# MSP430Geiger.net
KiCad netlist of a schematic drawn in EAGLE
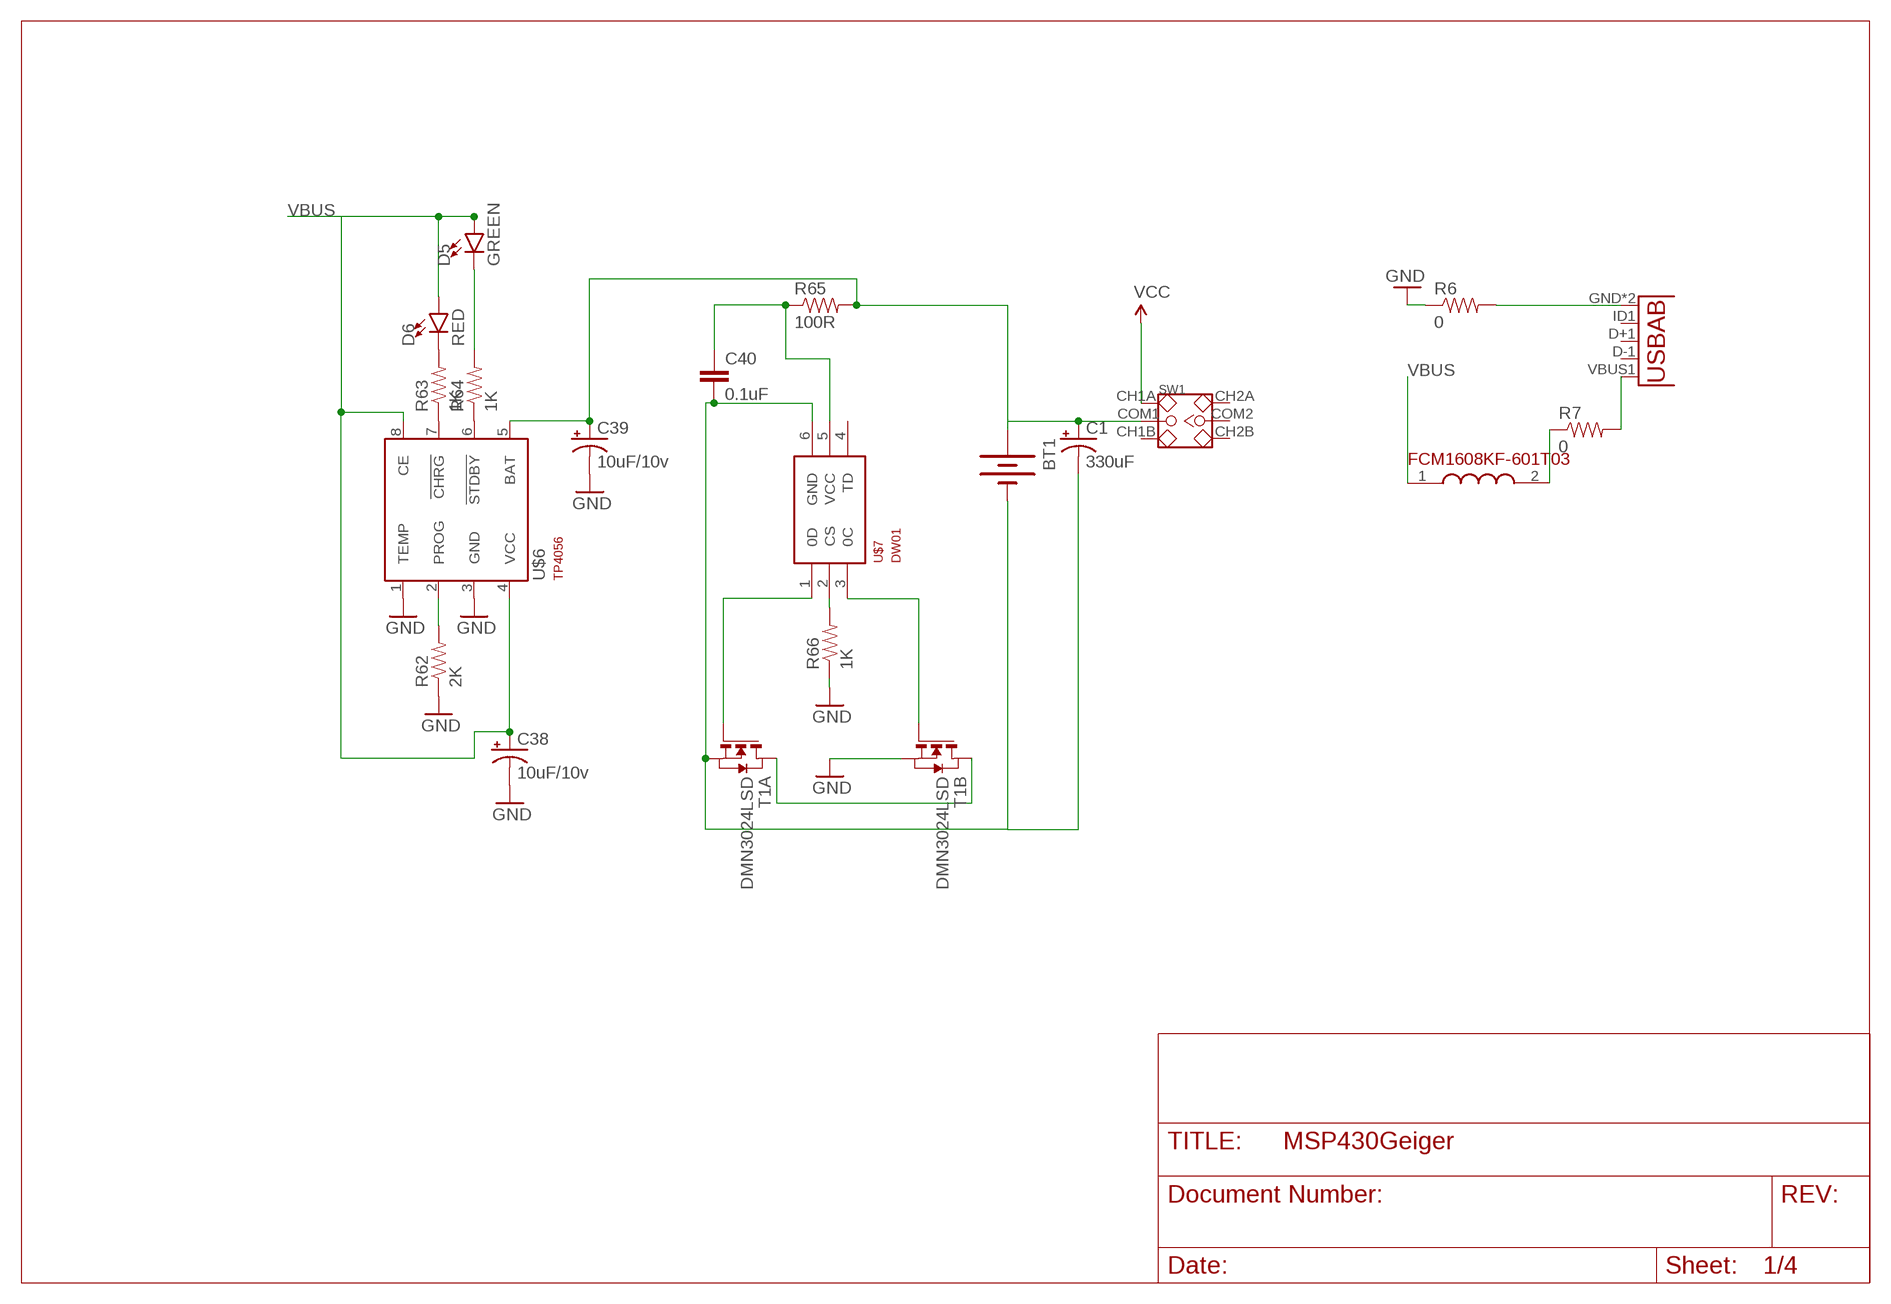
[diagram p0: schematic, sheet 1]
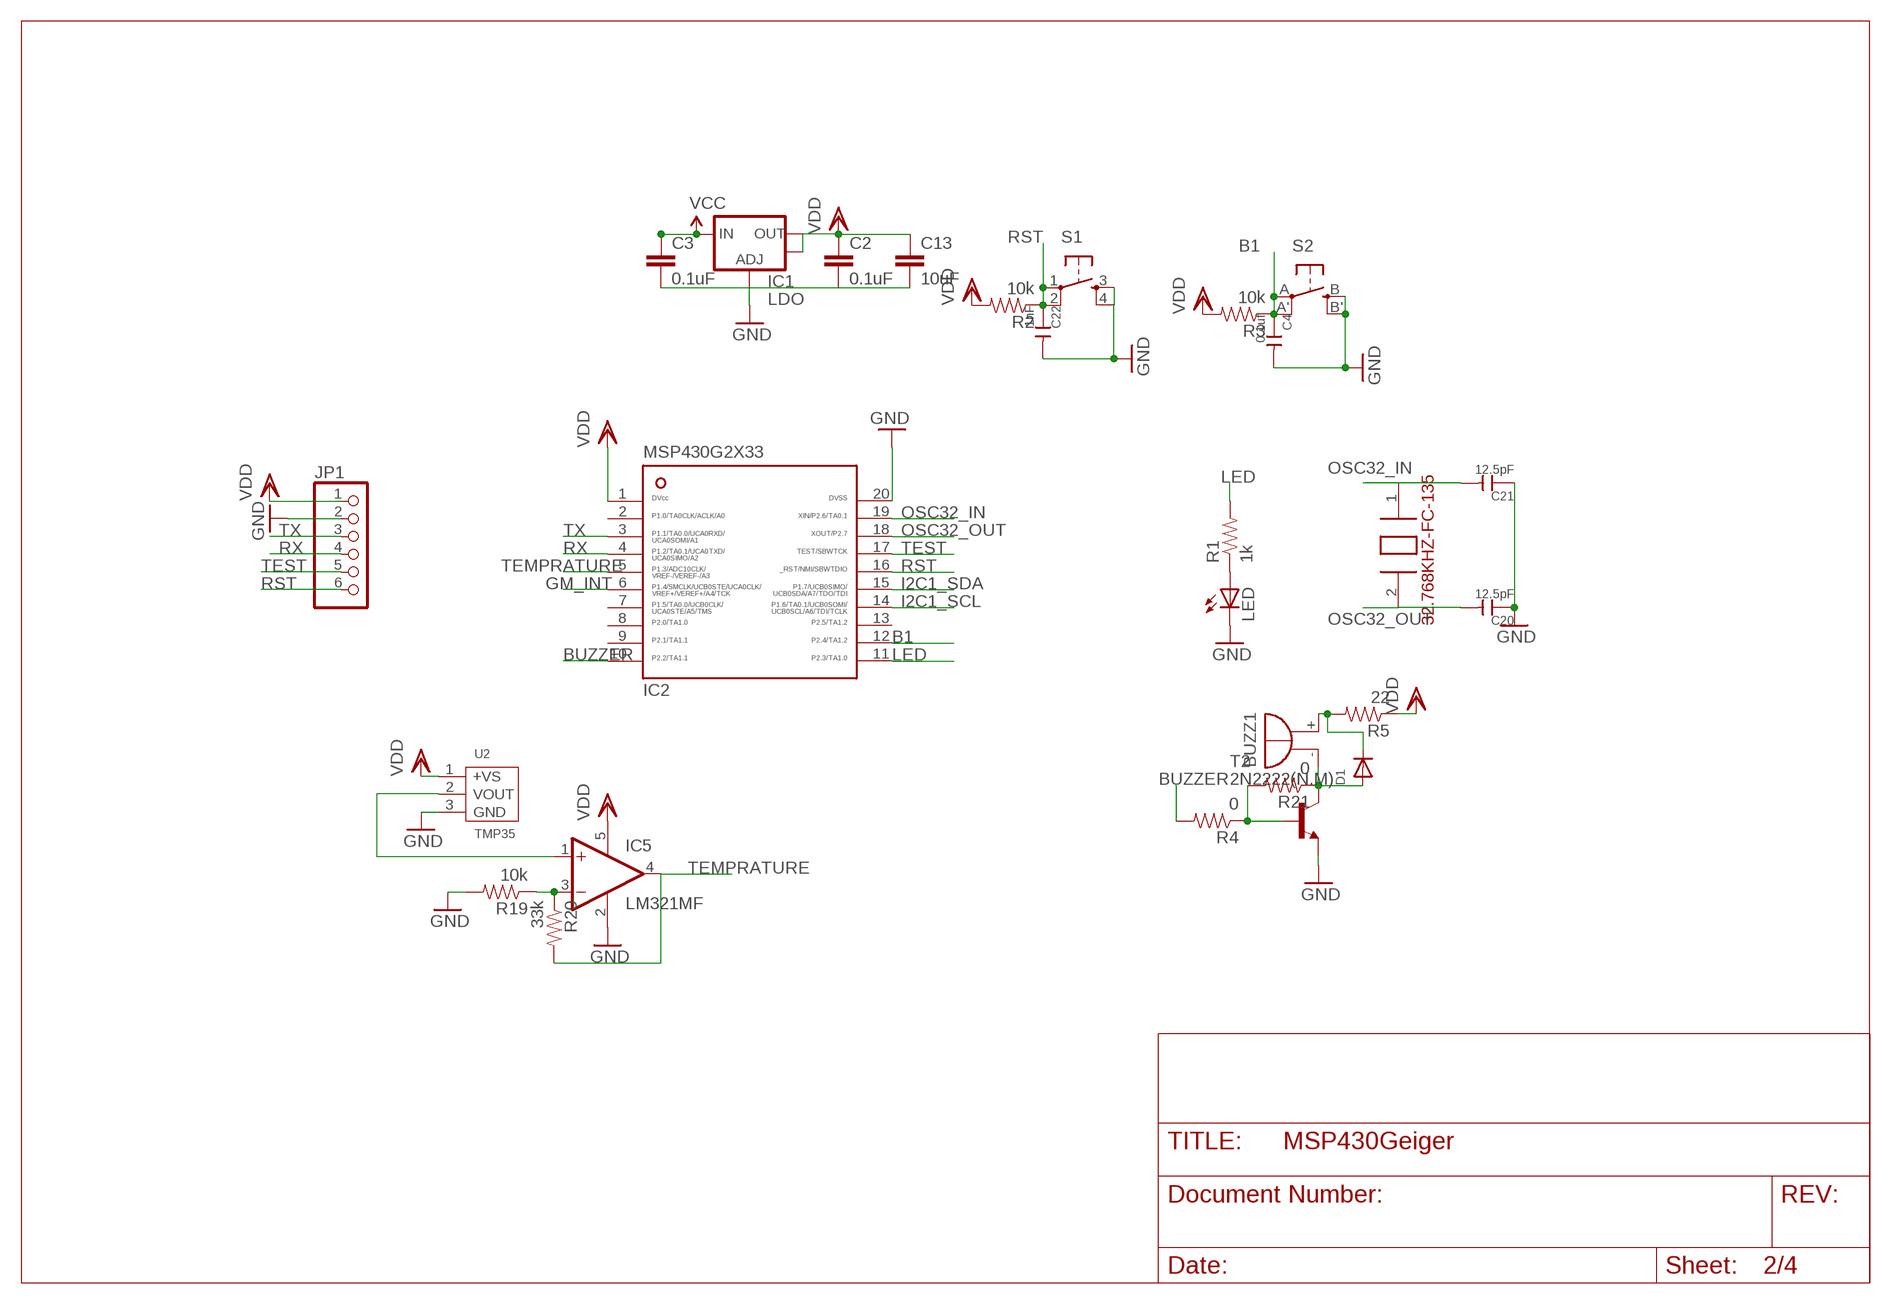
[diagram p1: schematic, sheet 2]
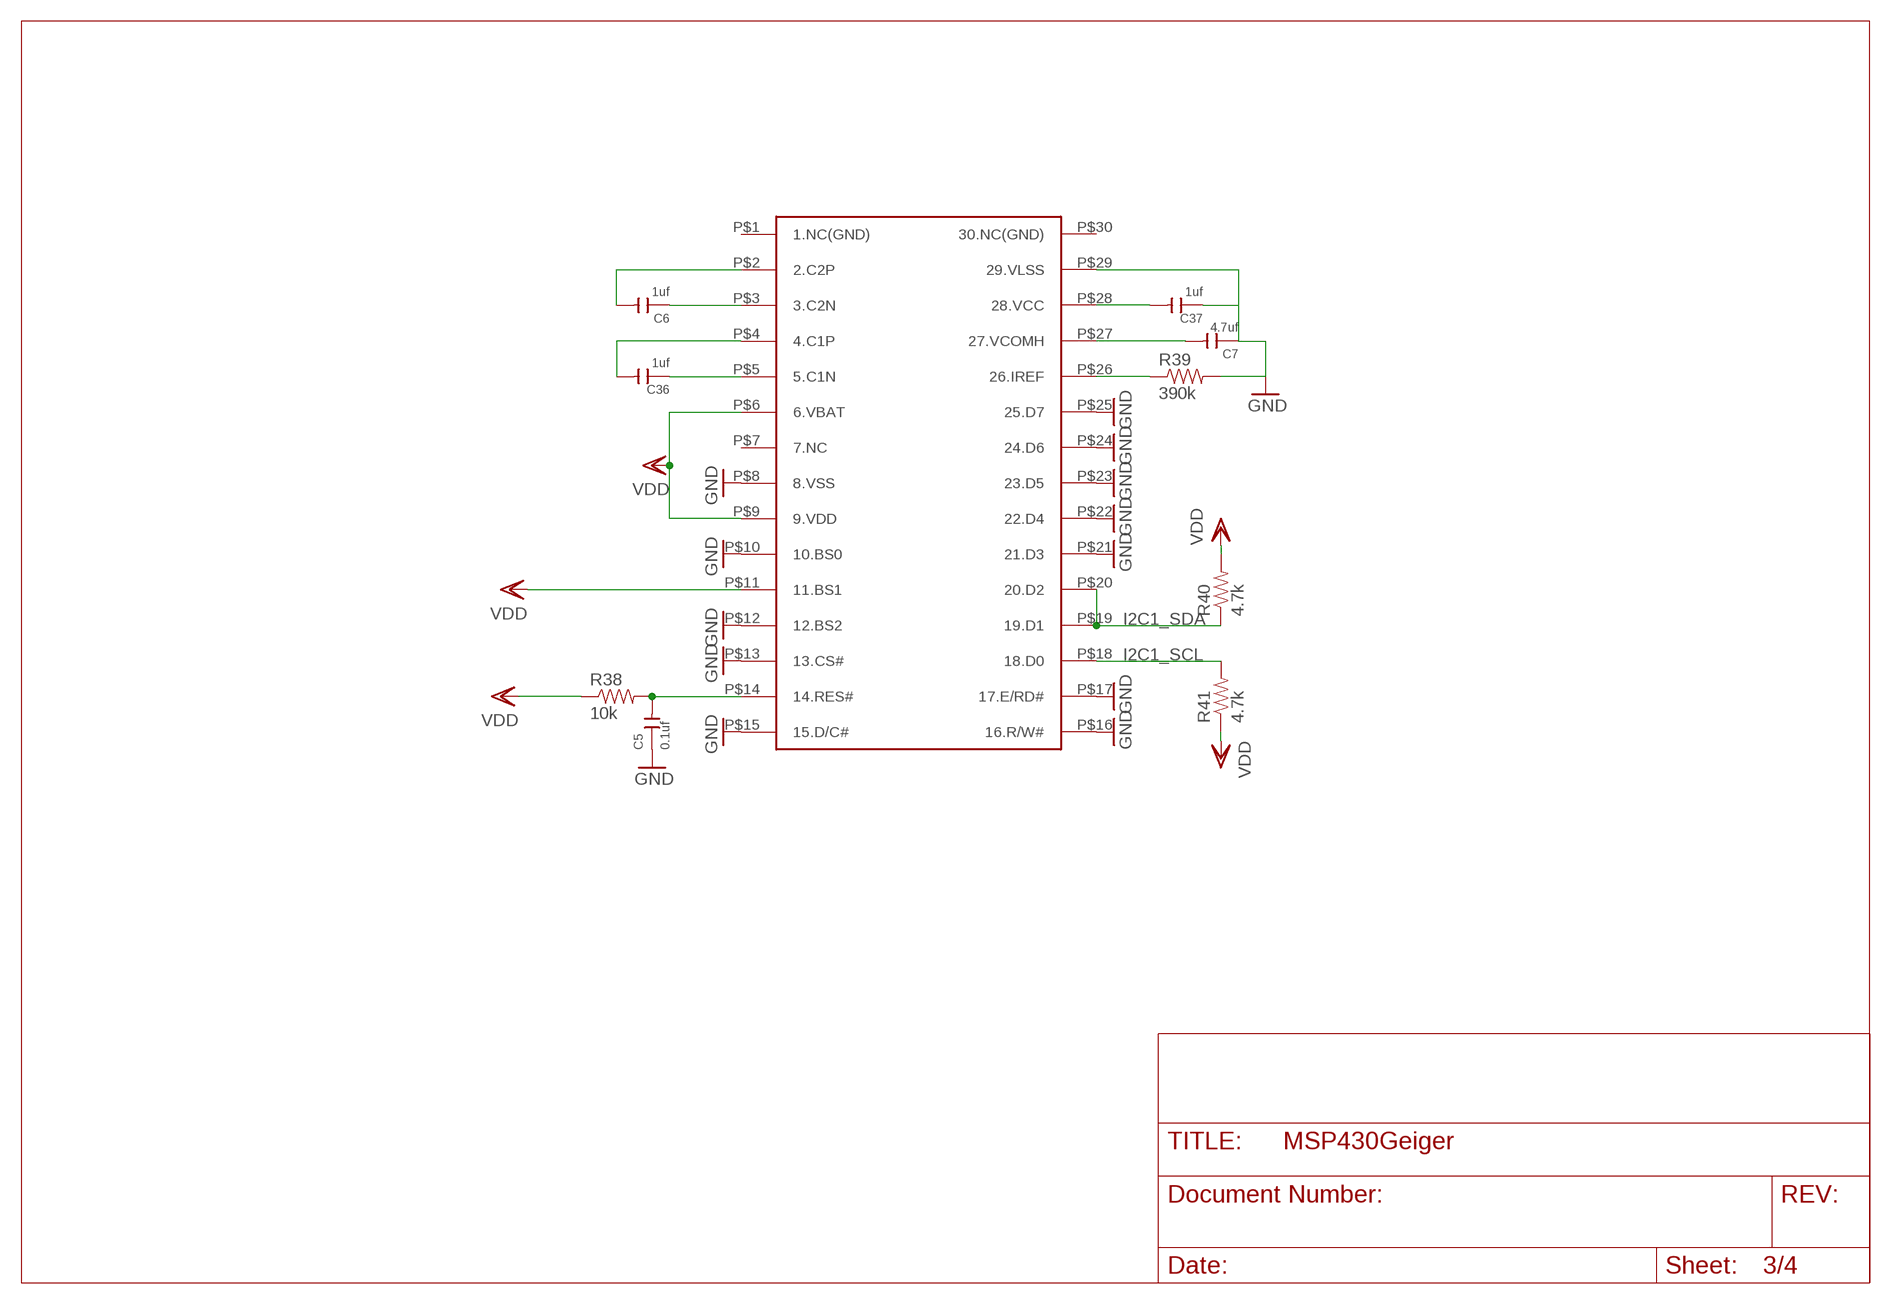
[diagram p2: schematic, sheet 3]
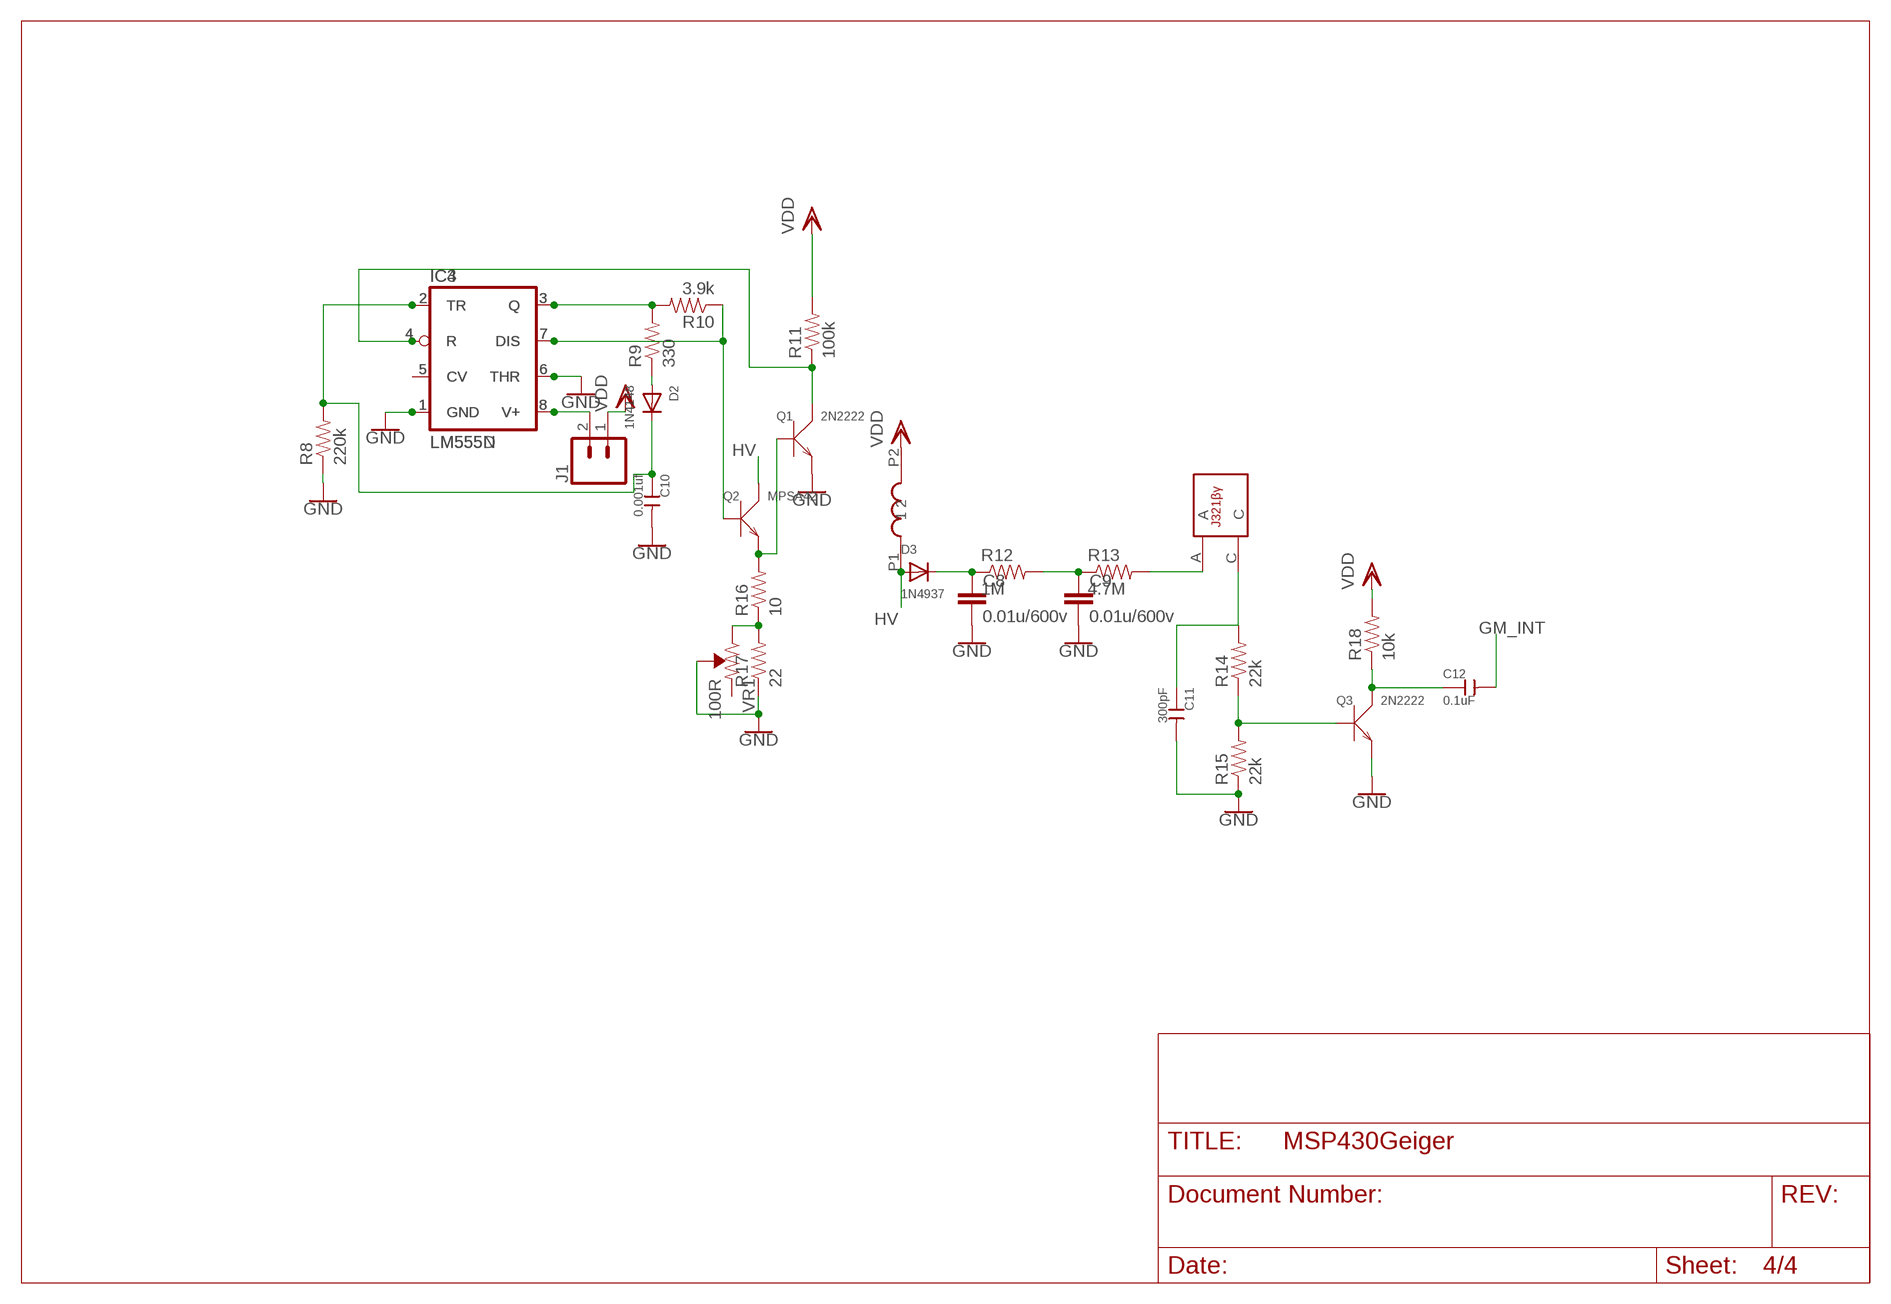
[diagram p3: schematic, sheet 4]

(export (version "E")
  (design (tool "Eeschema 10.0.6"))
  (components
    (comp (ref "C8")
      (value "0.01u/600v")
      (footprint "eagle-import:C15B5")
      (libsource (lib "eagle-import") (part "C15/5"))
    )
    (comp (ref "C9")
      (value "0.01u/600v")
      (footprint "eagle-import:C15B5")
      (libsource (lib "eagle-import") (part "C15/5"))
    )
    (comp (ref "C10")
      (value "0.001uf")
      (footprint "eagle-import:C0603")
      (fields (field (name "MPN") "CC0603KRX5R6BB475"))
      (libsource (lib "eagle-import") (part "CERAMIC-4.7UF-10V-10%-X5R(0603)"))
    )
    (comp (ref "C11")
      (value "300pF")
      (footprint "eagle-import:C0603")
      (fields (field (name "MPN") "CC0603KRX5R6BB475"))
      (libsource (lib "eagle-import") (part "CERAMIC-4.7UF-10V-10%-X5R(0603)"))
    )
    (comp (ref "C12")
      (value "0.1uF")
      (footprint "eagle-import:C0603")
      (fields (field (name "MPN") "CC0603KRX5R6BB475"))
      (libsource (lib "eagle-import") (part "CERAMIC-4.7UF-10V-10%-X5R(0603)"))
    )
    (comp (ref "D2")
      (value "1N4148")
      (footprint "eagle-import:SMADIODE")
      (libsource (lib "eagle-import") (part "DIODESMA"))
    )
    (comp (ref "D3")
      (value "1N4937")
      (footprint "eagle-import:SMADIODE")
      (libsource (lib "eagle-import") (part "DIODESMA"))
    )
    (comp (ref "IC3")
      (value "LM555D")
      (footprint "eagle-import:SO08")
      (libsource (lib "eagle-import") (part "555DLM"))
    )
    (comp (ref "IC4")
      (value "LM555N")
      (footprint "eagle-import:DIL08-ROUND")
      (libsource (lib "eagle-import") (part "555NLM"))
    )
    (comp (ref "J1")
      (value "CONN_02")
      (footprint "eagle-import:1X02")
      (libsource (lib "eagle-import") (part "CONN_02"))
    )
    (comp (ref "Q1")
      (value "2N2222")
      (footprint "eagle-import:SOT-23")
      (libsource (lib "eagle-import") (part "TRANSISTOR-NPN"))
    )
    (comp (ref "Q2")
      (value "MPSA42")
      (footprint "eagle-import:SOT-23")
      (libsource (lib "eagle-import") (part "TRANSISTOR-NPN"))
    )
    (comp (ref "Q3")
      (value "2N2222")
      (footprint "eagle-import:SOT-23")
      (libsource (lib "eagle-import") (part "TRANSISTOR-NPN"))
    )
    (comp (ref "R8")
      (value "220k")
      (footprint "eagle-import:0603")
      (libsource (lib "eagle-import") (part "0OHM1/10W5%(0603)"))
    )
    (comp (ref "R9")
      (value "330")
      (footprint "eagle-import:0603")
      (libsource (lib "eagle-import") (part "0OHM1/10W5%(0603)"))
    )
    (comp (ref "R10")
      (value "3.9k")
      (footprint "eagle-import:0603")
      (libsource (lib "eagle-import") (part "0OHM1/10W5%(0603)"))
    )
    (comp (ref "R11")
      (value "100k")
      (footprint "eagle-import:0603")
      (libsource (lib "eagle-import") (part "0OHM1/10W5%(0603)"))
    )
    (comp (ref "R12")
      (value "1M")
      (footprint "eagle-import:0603")
      (libsource (lib "eagle-import") (part "0OHM1/10W5%(0603)"))
    )
    (comp (ref "R13")
      (value "4.7M")
      (footprint "eagle-import:0603")
      (libsource (lib "eagle-import") (part "0OHM1/10W5%(0603)"))
    )
    (comp (ref "R14")
      (value "22k")
      (footprint "eagle-import:0603")
      (libsource (lib "eagle-import") (part "0OHM1/10W5%(0603)"))
    )
    (comp (ref "R15")
      (value "22k")
      (footprint "eagle-import:0603")
      (libsource (lib "eagle-import") (part "0OHM1/10W5%(0603)"))
    )
    (comp (ref "R16")
      (value "10")
      (footprint "eagle-import:0603")
      (libsource (lib "eagle-import") (part "0OHM1/10W5%(0603)"))
    )
    (comp (ref "R17")
      (value "22")
      (footprint "eagle-import:0603")
      (libsource (lib "eagle-import") (part "0OHM1/10W5%(0603)"))
    )
    (comp (ref "R18")
      (value "10k")
      (footprint "eagle-import:0603")
      (libsource (lib "eagle-import") (part "0OHM1/10W5%(0603)"))
    )
    (comp (ref "U$1")
      (value "J321βγ")
      (footprint "eagle-import:J321βγ")
      (libsource (lib "eagle-import") (part "J321βγ"))
    )
    (comp (ref "U$2")
      (value "10mF")
      (footprint "eagle-import:CD54")
      (libsource (lib "eagle-import") (part "CD54"))
    )
    (comp (ref "VR1")
      (value "100R")
      (footprint "eagle-import:TRIMPOT-SMD-3MM-CLOSED")
      (libsource (lib "eagle-import") (part "TRIMPOT-SMD-3MM-CLOSED-1/8W-20%"))
    )
    (comp (ref "BT1")
      (value "BATTERYLIPO-TABS")
      (footprint "eagle-import:LIPO-110-TABS")
      (libsource (lib "eagle-import") (part "BATTERYLIPO-TABS"))
    )
    (comp (ref "C1")
      (value "330uF")
      (footprint "eagle-import:E3,5-8")
      (libsource (lib "eagle-import") (part "CPOL-USE3.5-8"))
    )
    (comp (ref "C38")
      (value "10uF/10v")
      (footprint "eagle-import:EIA3216-KIT")
      (libsource (lib "eagle-import") (part "CAP_POL1206-KIT"))
    )
    (comp (ref "C39")
      (value "10uF/10v")
      (footprint "eagle-import:EIA3216-KIT")
      (libsource (lib "eagle-import") (part "CAP_POL1206-KIT"))
    )
    (comp (ref "C40")
      (value "0.1uF")
      (footprint "eagle-import:0603-CAP")
      (libsource (lib "eagle-import") (part "0.1UF-100V-10%(0603)"))
    )
    (comp (ref "D5")
      (value "GREEN")
      (footprint "eagle-import:LED-0603")
      (libsource (lib "eagle-import") (part "LED-BLUE0603"))
    )
    (comp (ref "D6")
      (value "RED")
      (footprint "eagle-import:LED-0603")
      (libsource (lib "eagle-import") (part "LED-BLUE0603"))
    )
    (comp (ref "R6")
      (value "0")
      (footprint "eagle-import:0805")
      (libsource (lib "eagle-import") (part "RESISTOR0805-RES"))
    )
    (comp (ref "R7")
      (value "0")
      (footprint "eagle-import:0805")
      (libsource (lib "eagle-import") (part "RESISTOR0805-RES"))
    )
    (comp (ref "R62")
      (value "2K")
      (footprint "eagle-import:0603-RES")
      (libsource (lib "eagle-import") (part "1KOHM1/10W1%(0603)"))
    )
    (comp (ref "R63")
      (value "1K")
      (footprint "eagle-import:0603-RES")
      (libsource (lib "eagle-import") (part "1KOHM1/10W1%(0603)"))
    )
    (comp (ref "R64")
      (value "1K")
      (footprint "eagle-import:0603-RES")
      (libsource (lib "eagle-import") (part "1KOHM1/10W1%(0603)"))
    )
    (comp (ref "R65")
      (value "100R")
      (footprint "eagle-import:0603-RES")
      (libsource (lib "eagle-import") (part "1KOHM1/10W1%(0603)"))
    )
    (comp (ref "R66")
      (value "1K")
      (footprint "eagle-import:0603-RES")
      (libsource (lib "eagle-import") (part "1KOHM1/10W1%(0603)"))
    )
    (comp (ref "SW1")
      (value "SMD-TOGGLE-SWITCH-2CH(2X3P-7X3.5MM)")
      (footprint "eagle-import:SW6-2.54-SMD-7.0X3.5X1.5MM")
      (libsource (lib "eagle-import") (part "SMD-TOGGLE-SWITCH-2CH(2X3P-7X3.5MM)"))
    )
    (comp (ref "T1")
      (value "DMN3024LSD")
      (footprint "eagle-import:TSSOP-8")
      (libsource (lib "eagle-import") (part "DMN3024LSD"))
    )
    (comp (ref "U$4")
      (value "FCM1608KF-601T03")
      (footprint "eagle-import:FCM1608KF-601T03")
      (libsource (lib "eagle-import") (part "FCM1608KF-601T03"))
    )
    (comp (ref "U$6")
      (value "TP4056")
      (footprint "eagle-import:SOT23-8")
      (libsource (lib "eagle-import") (part "TP4056"))
    )
    (comp (ref "U$7")
      (value "DW01")
      (footprint "eagle-import:SOT23-6")
      (libsource (lib "eagle-import") (part "DW01"))
    )
    (comp (ref "U1")
      (value "USB\"\"")
      (footprint "eagle-import:USB-MICRO-SMD")
      (libsource (lib "eagle-import") (part "USB{dblquote}{dblquote}"))
    )
    (comp (ref "C5")
      (value "0.1uf")
      (footprint "eagle-import:C0603")
      (fields (field (name "MPN") "CC0603KRX5R6BB475"))
      (libsource (lib "eagle-import") (part "CERAMIC-4.7UF-10V-10%-X5R(0603)"))
    )
    (comp (ref "C6")
      (value "1uf")
      (footprint "eagle-import:C0603")
      (fields (field (name "MPN") "CC0603KRX5R6BB475"))
      (libsource (lib "eagle-import") (part "CERAMIC-4.7UF-10V-10%-X5R(0603)"))
    )
    (comp (ref "C7")
      (value "4.7uf")
      (footprint "eagle-import:C0603")
      (fields (field (name "MPN") "CC0603KRX5R6BB475"))
      (libsource (lib "eagle-import") (part "CERAMIC-4.7UF-10V-10%-X5R(0603)"))
    )
    (comp (ref "C36")
      (value "1uf")
      (footprint "eagle-import:C0603")
      (fields (field (name "MPN") "CC0603KRX5R6BB475"))
      (libsource (lib "eagle-import") (part "CERAMIC-4.7UF-10V-10%-X5R(0603)"))
    )
    (comp (ref "C37")
      (value "1uf")
      (footprint "eagle-import:C0603")
      (fields (field (name "MPN") "CC0603KRX5R6BB475"))
      (libsource (lib "eagle-import") (part "CERAMIC-4.7UF-10V-10%-X5R(0603)"))
    )
    (comp (ref "R38")
      (value "10k")
      (footprint "eagle-import:0603")
      (libsource (lib "eagle-import") (part "0OHM1/10W5%(0603)"))
    )
    (comp (ref "R39")
      (value "390k")
      (footprint "eagle-import:0603")
      (libsource (lib "eagle-import") (part "0OHM1/10W5%(0603)"))
    )
    (comp (ref "R40")
      (value "4.7k")
      (footprint "eagle-import:0603")
      (libsource (lib "eagle-import") (part "0OHM1/10W5%(0603)"))
    )
    (comp (ref "R41")
      (value "4.7k")
      (footprint "eagle-import:0603")
      (libsource (lib "eagle-import") (part "0OHM1/10W5%(0603)"))
    )
    (comp (ref "U$18")
      (value "ER-OLED0.96")
      (footprint "eagle-import:ER-OLED0.96")
      (libsource (lib "eagle-import") (part "ER-OLED0.96"))
    )
    (comp (ref "BUZZ1")
      (value "F/QMBIII")
      (footprint "eagle-import:F_QMBIII")
      (libsource (lib "eagle-import") (part "F/QMBIII"))
    )
    (comp (ref "C2")
      (value "0.1uF")
      (footprint "eagle-import:0603-CAP")
      (libsource (lib "eagle-import") (part "0.1UF-25V(+80/-20%)(0603)"))
    )
    (comp (ref "C3")
      (value "0.1uF")
      (footprint "eagle-import:0603-CAP")
      (libsource (lib "eagle-import") (part "0.1UF-25V(+80/-20%)(0603)"))
    )
    (comp (ref "C4")
      (value "0.1uf")
      (footprint "eagle-import:C0603")
      (fields (field (name "MPN") "CC0603KRX5R6BB475"))
      (libsource (lib "eagle-import") (part "CERAMIC-4.7UF-10V-10%-X5R(0603)"))
    )
    (comp (ref "C13")
      (value "10uF")
      (footprint "eagle-import:0603-CAP")
      (libsource (lib "eagle-import") (part "0.1UF-25V(+80/-20%)(0603)"))
    )
    (comp (ref "C20")
      (value "12.5pF")
      (footprint "eagle-import:C0603")
      (fields (field (name "MPN") "CC0603KRX5R6BB475"))
      (libsource (lib "eagle-import") (part "CERAMIC-4.7UF-10V-10%-X5R(0603)"))
    )
    (comp (ref "C21")
      (value "12.5pF")
      (footprint "eagle-import:C0603")
      (fields (field (name "MPN") "CC0603KRX5R6BB475"))
      (libsource (lib "eagle-import") (part "CERAMIC-4.7UF-10V-10%-X5R(0603)"))
    )
    (comp (ref "C22")
      (value "1nF")
      (footprint "eagle-import:C0603")
      (fields (field (name "MPN") "CC0603KRX5R6BB475"))
      (libsource (lib "eagle-import") (part "CERAMIC-4.7UF-10V-10%-X5R(0603)"))
    )
    (comp (ref "D1")
      (value "DIODESMA")
      (footprint "eagle-import:SMADIODE")
      (libsource (lib "eagle-import") (part "DIODESMA"))
    )
    (comp (ref "IC1")
      (value "LDO")
      (footprint "eagle-import:SOT223")
      (libsource (lib "eagle-import") (part "V_REG_LM1117SOT223"))
    )
    (comp (ref "IC2")
      (value "MSP430")
      (footprint "eagle-import:PW20")
      (libsource (lib "eagle-import") (part "MSP430G2X33-20PW20"))
    )
    (comp (ref "IC5")
      (value "LM321MF")
      (footprint "eagle-import:SOT23-5")
      (libsource (lib "eagle-import") (part "LM321?MF"))
    )
    (comp (ref "JP1")
      (value "PINHD-1X6")
      (footprint "eagle-import:1X06")
      (libsource (lib "eagle-import") (part "PINHD-1X6"))
    )
    (comp (ref "LED")
      (value "LEDCHIP-LED0805")
      (footprint "eagle-import:CHIP-LED0805")
      (libsource (lib "eagle-import") (part "LEDCHIP-LED0805"))
    )
    (comp (ref "R1")
      (value "1k")
      (footprint "eagle-import:0805")
      (libsource (lib "eagle-import") (part "0.22OHM1/4W1%(0805)"))
    )
    (comp (ref "R2")
      (value "10k")
      (footprint "eagle-import:0603")
      (libsource (lib "eagle-import") (part "0OHM1/10W5%(0603)"))
    )
    (comp (ref "R3")
      (value "10k")
      (footprint "eagle-import:0603")
      (libsource (lib "eagle-import") (part "0OHM1/10W5%(0603)"))
    )
    (comp (ref "R4")
      (value "0")
      (footprint "eagle-import:0805")
      (libsource (lib "eagle-import") (part "0.22OHM1/4W1%(0805)"))
    )
    (comp (ref "R5")
      (value "22")
      (footprint "eagle-import:0805")
      (libsource (lib "eagle-import") (part "0.22OHM1/4W1%(0805)"))
    )
    (comp (ref "R19")
      (value "10k")
      (footprint "eagle-import:0805")
      (libsource (lib "eagle-import") (part "0.22OHM1/4W1%(0805)"))
    )
    (comp (ref "R20")
      (value "33k")
      (footprint "eagle-import:0805")
      (libsource (lib "eagle-import") (part "0.22OHM1/4W1%(0805)"))
    )
    (comp (ref "R21")
      (value "0")
      (footprint "eagle-import:0805")
      (libsource (lib "eagle-import") (part "0.22OHM1/4W1%(0805)"))
    )
    (comp (ref "S1")
      (value "TAC_SWITCHSMD")
      (footprint "eagle-import:TACTILE_SWITCH_SMD")
      (libsource (lib "eagle-import") (part "TAC_SWITCHSMD"))
    )
    (comp (ref "S2")
      (value "SPST_TACT-EVQQ2")
      (footprint "eagle-import:EVQ-Q2")
      (libsource (lib "eagle-import") (part "SPST_TACT-EVQQ2"))
    )
    (comp (ref "T2")
      (value "2N2222(N.M)")
      (footprint "eagle-import:SOT23-EBC")
      (libsource (lib "eagle-import") (part "-NPN-SOT23-EBC"))
    )
    (comp (ref "U$8")
      (value "32.768KHZ-FC-135")
      (footprint "eagle-import:32.768KHZ-FC-135")
      (libsource (lib "eagle-import") (part "32.768KHZ-FC-135"))
    )
    (comp (ref "U2")
      (value "TMP35")
      (footprint "eagle-import:TO-92-3")
      (fields (field (name "MPN") "TEM36"))
      (libsource (lib "eagle-import") (part "TEMPERATURE-TEM36(TO-92)"))
    )
  )
  (nets
    (net (code "1") (name "B1") (class "Default")
      (node (ref "C4") (pin "1") (pinfunction "1_1") (pintype "passive"))
      (node (ref "IC2") (pin "12") (pinfunction "12_12") (pintype "bidirectional"))
      (node (ref "R3") (pin "1") (pinfunction "1_1") (pintype "passive"))
      (node (ref "S2") (pin "A") (pinfunction "P_A") (pintype "passive"))
      (node (ref "S2") (pin "A'") (pinfunction "P1_A'") (pintype "passive"))
    )
    (net (code "2") (name "BUZZER") (class "Default")
      (node (ref "IC2") (pin "10") (pinfunction "10_10") (pintype "bidirectional"))
      (node (ref "R4") (pin "2") (pinfunction "2_2") (pintype "passive"))
    )
    (net (code "3") (name "GM_INT") (class "Default")
      (node (ref "C12") (pin "2") (pinfunction "2_2") (pintype "passive"))
      (node (ref "IC2") (pin "6") (pinfunction "6_6") (pintype "bidirectional"))
    )
    (net (code "4") (name "GND") (class "Default")
      (node (ref "C10") (pin "2") (pinfunction "2_2") (pintype "passive"))
      (node (ref "C11") (pin "2") (pinfunction "2_2") (pintype "passive"))
      (node (ref "C13") (pin "2") (pinfunction "2_2") (pintype "passive"))
      (node (ref "C2") (pin "2") (pinfunction "2_2") (pintype "passive"))
      (node (ref "C20") (pin "1") (pinfunction "1_1") (pintype "passive"))
      (node (ref "C21") (pin "1") (pinfunction "1_1") (pintype "passive"))
      (node (ref "C22") (pin "2") (pinfunction "2_2") (pintype "passive"))
      (node (ref "C3") (pin "2") (pinfunction "2_2") (pintype "passive"))
      (node (ref "C37") (pin "1") (pinfunction "1_1") (pintype "passive"))
      (node (ref "C38") (pin "C") (pinfunction "-_C") (pintype "passive"))
      (node (ref "C39") (pin "C") (pinfunction "-_C") (pintype "passive"))
      (node (ref "C4") (pin "2") (pinfunction "2_2") (pintype "passive"))
      (node (ref "C5") (pin "1") (pinfunction "1_1") (pintype "passive"))
      (node (ref "C7") (pin "1") (pinfunction "1_1") (pintype "passive"))
      (node (ref "C8") (pin "2") (pinfunction "2_2") (pintype "passive"))
      (node (ref "C9") (pin "2") (pinfunction "2_2") (pintype "passive"))
      (node (ref "IC1") (pin "1") (pinfunction "ADJ_1") (pintype "input"))
      (node (ref "IC2") (pin "20") (pinfunction "20_20") (pintype "bidirectional"))
      (node (ref "IC3") (pin "1") (pinfunction "GND_1") (pintype "power_in"))
      (node (ref "IC3") (pin "6") (pinfunction "THR_6") (pintype "input"))
      (node (ref "IC4") (pin "1") (pinfunction "GND_1") (pintype "power_in"))
      (node (ref "IC4") (pin "6") (pinfunction "THR_6") (pintype "input"))
      (node (ref "IC5") (pin "2") (pinfunction "V-_2") (pintype "power_in"))
      (node (ref "JP1") (pin "2") (pinfunction "2_2") (pintype "passive"))
      (node (ref "LED") (pin "C") (pinfunction "C_C") (pintype "passive"))
      (node (ref "Q1") (pin "2") (pinfunction "E_2") (pintype "passive"))
      (node (ref "Q3") (pin "2") (pinfunction "E_2") (pintype "passive"))
      (node (ref "R15") (pin "1") (pinfunction "1_1") (pintype "passive"))
      (node (ref "R17") (pin "1") (pinfunction "1_1") (pintype "passive"))
      (node (ref "R19") (pin "2") (pinfunction "2_2") (pintype "passive"))
      (node (ref "R39") (pin "2") (pinfunction "2_2") (pintype "passive"))
      (node (ref "R6") (pin "1") (pinfunction "1_1") (pintype "passive"))
      (node (ref "R62") (pin "1") (pinfunction "1_1") (pintype "passive"))
      (node (ref "R66") (pin "1") (pinfunction "1_1") (pintype "passive"))
      (node (ref "R8") (pin "1") (pinfunction "1_1") (pintype "passive"))
      (node (ref "S1") (pin "3") (pinfunction "3_3") (pintype "passive"))
      (node (ref "S1") (pin "4") (pinfunction "4_4") (pintype "passive"))
      (node (ref "S2") (pin "B") (pinfunction "S_B") (pintype "passive"))
      (node (ref "S2") (pin "B'") (pinfunction "S1_B'") (pintype "passive"))
      (node (ref "T1") (pin "6") (pinfunction "S_6") (pintype "passive"))
      (node (ref "T1") (pin "7") (pinfunction "S_7") (pintype "passive"))
      (node (ref "T2") (pin "E") (pinfunction "E_E") (pintype "passive"))
      (node (ref "U$18") (pin "P$10") (pinfunction "10.BS0_P$10") (pintype "bidirectional"))
      (node (ref "U$18") (pin "P$12") (pinfunction "12.BS2_P$12") (pintype "bidirectional"))
      (node (ref "U$18") (pin "P$13") (pinfunction "13.CS#_P$13") (pintype "bidirectional"))
      (node (ref "U$18") (pin "P$15") (pinfunction "15.D/C#_P$15") (pintype "bidirectional"))
      (node (ref "U$18") (pin "P$16") (pinfunction "16.R/W#_P$16") (pintype "bidirectional"))
      (node (ref "U$18") (pin "P$17") (pinfunction "17.E/RD#_P$17") (pintype "bidirectional"))
      (node (ref "U$18") (pin "P$21") (pinfunction "21.D3_P$21") (pintype "bidirectional"))
      (node (ref "U$18") (pin "P$22") (pinfunction "22.D4_P$22") (pintype "bidirectional"))
      (node (ref "U$18") (pin "P$23") (pinfunction "23.D5_P$23") (pintype "bidirectional"))
      (node (ref "U$18") (pin "P$24") (pinfunction "24.D6_P$24") (pintype "bidirectional"))
      (node (ref "U$18") (pin "P$25") (pinfunction "25.D7_P$25") (pintype "bidirectional"))
      (node (ref "U$18") (pin "P$29") (pinfunction "29.VLSS_P$29") (pintype "bidirectional"))
      (node (ref "U$18") (pin "P$8") (pinfunction "8.VSS_P$8") (pintype "bidirectional"))
      (node (ref "U$6") (pin "1") (pinfunction "TEMP_1") (pintype "bidirectional"))
      (node (ref "U$6") (pin "3") (pinfunction "GND_3") (pintype "bidirectional"))
      (node (ref "U2") (pin "3") (pinfunction "GND_3") (pintype "bidirectional"))
      (node (ref "VR1") (pin "2") (pinfunction "WIPER_2") (pintype "passive"))
    )
    (net (code "5") (name "HV") (class "Default")
      (node (ref "D3") (pin "A") (pinfunction "A_A") (pintype "passive"))
      (node (ref "Q2") (pin "3") (pinfunction "C_3") (pintype "passive"))
      (node (ref "U$2") (pin "P1") (pinfunction "1_P1") (pintype "bidirectional"))
    )
    (net (code "6") (name "I2C1_SCL") (class "Default")
      (node (ref "IC2") (pin "14") (pinfunction "14_14") (pintype "bidirectional"))
      (node (ref "R41") (pin "2") (pinfunction "2_2") (pintype "passive"))
      (node (ref "U$18") (pin "P$18") (pinfunction "18.D0_P$18") (pintype "bidirectional"))
    )
    (net (code "7") (name "I2C1_SDA") (class "Default")
      (node (ref "IC2") (pin "15") (pinfunction "15_15") (pintype "bidirectional"))
      (node (ref "R40") (pin "1") (pinfunction "1_1") (pintype "passive"))
      (node (ref "U$18") (pin "P$19") (pinfunction "19.D1_P$19") (pintype "bidirectional"))
      (node (ref "U$18") (pin "P$20") (pinfunction "20.D2_P$20") (pintype "bidirectional"))
    )
    (net (code "8") (name "LED") (class "Default")
      (node (ref "IC2") (pin "11") (pinfunction "11_11") (pintype "bidirectional"))
      (node (ref "R1") (pin "2") (pinfunction "2_2") (pintype "passive"))
    )
    (net (code "9") (name "Net-(BUZZ1-+)") (class "Default")
      (node (ref "BUZZ1") (pin "-") (pinfunction "+_-") (pintype "passive"))
      (node (ref "D1") (pin "A") (pinfunction "A_A") (pintype "passive"))
      (node (ref "R21") (pin "1") (pinfunction "1_1") (pintype "passive"))
      (node (ref "T2") (pin "C") (pinfunction "C_C") (pintype "passive"))
    )
    (net (code "10") (name "Net-(BUZZ1--)") (class "Default")
      (node (ref "BUZZ1") (pin "+") (pinfunction "-_+") (pintype "passive"))
      (node (ref "D1") (pin "C") (pinfunction "C_C") (pintype "passive"))
      (node (ref "R5") (pin "2") (pinfunction "2_2") (pintype "passive"))
    )
    (net (code "11") (name "Net-(C8-Pad1)") (class "Default")
      (node (ref "C8") (pin "1") (pinfunction "1_1") (pintype "passive"))
      (node (ref "D3") (pin "C") (pinfunction "C_C") (pintype "passive"))
      (node (ref "R12") (pin "1") (pinfunction "1_1") (pintype "passive"))
    )
    (net (code "12") (name "Net-(C9-Pad1)") (class "Default")
      (node (ref "C9") (pin "1") (pinfunction "1_1") (pintype "passive"))
      (node (ref "R12") (pin "2") (pinfunction "2_2") (pintype "passive"))
      (node (ref "R13") (pin "1") (pinfunction "1_1") (pintype "passive"))
    )
    (net (code "13") (name "Net-(C11-Pad1)") (class "Default")
      (node (ref "C11") (pin "1") (pinfunction "1_1") (pintype "passive"))
      (node (ref "R14") (pin "2") (pinfunction "2_2") (pintype "passive"))
      (node (ref "U$1") (pin "C") (pinfunction "C_C") (pintype "bidirectional"))
    )
    (net (code "14") (name "Net-(C39-+)") (class "Default")
      (node (ref "BT1") (pin "+") (pinfunction "+_+") (pintype "power_in"))
      (node (ref "C1") (pin "+") (pinfunction "+_+") (pintype "passive"))
      (node (ref "C39") (pin "A") (pinfunction "+_A") (pintype "passive"))
      (node (ref "R65") (pin "2") (pinfunction "2_2") (pintype "passive"))
      (node (ref "SW1") (pin "COM1") (pinfunction "COM1_COM1") (pintype "bidirectional"))
      (node (ref "U$6") (pin "5") (pinfunction "BAT_5") (pintype "bidirectional"))
    )
    (net (code "15") (name "Net-(D2-PadA)") (class "Default")
      (node (ref "D2") (pin "A") (pinfunction "A_A") (pintype "passive"))
      (node (ref "R9") (pin "1") (pinfunction "1_1") (pintype "passive"))
    )
    (net (code "16") (name "Net-(D5-PadC)") (class "Default")
      (node (ref "D5") (pin "C") (pinfunction "C_C") (pintype "passive"))
      (node (ref "R64") (pin "2") (pinfunction "2_2") (pintype "passive"))
    )
    (net (code "17") (name "Net-(D6-PadC)") (class "Default")
      (node (ref "D6") (pin "C") (pinfunction "C_C") (pintype "passive"))
      (node (ref "R63") (pin "2") (pinfunction "2_2") (pintype "passive"))
    )
    (net (code "18") (name "Net-(IC3-CV)") (class "Default")
      (node (ref "IC3") (pin "5") (pinfunction "CV_5") (pintype "input"))
      (node (ref "IC4") (pin "5") (pinfunction "CV_5") (pintype "input"))
    )
    (net (code "19") (name "Net-(IC3-DIS)") (class "Default")
      (node (ref "IC3") (pin "7") (pinfunction "DIS_7") (pintype "input"))
      (node (ref "IC4") (pin "7") (pinfunction "DIS_7") (pintype "input"))
      (node (ref "Q2") (pin "1") (pinfunction "B_1") (pintype "passive"))
      (node (ref "R10") (pin "1") (pinfunction "1_1") (pintype "passive"))
    )
    (net (code "20") (name "Net-(IC3-Q)") (class "Default")
      (node (ref "IC3") (pin "3") (pinfunction "Q_3") (pintype "output"))
      (node (ref "IC4") (pin "3") (pinfunction "Q_3") (pintype "output"))
      (node (ref "R10") (pin "2") (pinfunction "2_2") (pintype "passive"))
      (node (ref "R9") (pin "2") (pinfunction "2_2") (pintype "passive"))
    )
    (net (code "21") (name "Net-(IC3-R)") (class "Default")
      (node (ref "IC3") (pin "4") (pinfunction "R_4") (pintype "input"))
      (node (ref "IC4") (pin "4") (pinfunction "R_4") (pintype "input"))
      (node (ref "Q1") (pin "3") (pinfunction "C_3") (pintype "passive"))
      (node (ref "R11") (pin "1") (pinfunction "1_1") (pintype "passive"))
    )
    (net (code "22") (name "Net-(IC3-TR)") (class "Default")
      (node (ref "C10") (pin "1") (pinfunction "1_1") (pintype "passive"))
      (node (ref "D2") (pin "C") (pinfunction "C_C") (pintype "passive"))
      (node (ref "IC3") (pin "2") (pinfunction "TR_2") (pintype "input"))
      (node (ref "IC4") (pin "2") (pinfunction "TR_2") (pintype "input"))
      (node (ref "R8") (pin "2") (pinfunction "2_2") (pintype "passive"))
    )
    (net (code "23") (name "Net-(IC3-V+)") (class "Default")
      (node (ref "IC3") (pin "8") (pinfunction "V+_8") (pintype "power_in"))
      (node (ref "IC4") (pin "8") (pinfunction "V+_8") (pintype "power_in"))
      (node (ref "J1") (pin "2") (pinfunction "2_2") (pintype "passive"))
    )
    (net (code "24") (name "Net-(IC5-+IN)") (class "Default")
      (node (ref "IC5") (pin "1") (pinfunction "+IN_1") (pintype "input"))
      (node (ref "U2") (pin "2") (pinfunction "VOUT_2") (pintype "bidirectional"))
    )
    (net (code "25") (name "Net-(IC5--IN)") (class "Default")
      (node (ref "IC5") (pin "3") (pinfunction "-IN_3") (pintype "input"))
      (node (ref "R19") (pin "1") (pinfunction "1_1") (pintype "passive"))
      (node (ref "R20") (pin "1") (pinfunction "1_1") (pintype "passive"))
    )
    (net (code "26") (name "Net-(LED-PadA)") (class "Default")
      (node (ref "LED") (pin "A") (pinfunction "A_A") (pintype "passive"))
      (node (ref "R1") (pin "1") (pinfunction "1_1") (pintype "passive"))
    )
    (net (code "27") (name "Net-(Q1-B)") (class "Default")
      (node (ref "Q1") (pin "1") (pinfunction "B_1") (pintype "passive"))
      (node (ref "Q2") (pin "2") (pinfunction "E_2") (pintype "passive"))
      (node (ref "R16") (pin "2") (pinfunction "2_2") (pintype "passive"))
    )
    (net (code "28") (name "Net-(Q3-B)") (class "Default")
      (node (ref "Q3") (pin "1") (pinfunction "B_1") (pintype "passive"))
      (node (ref "R14") (pin "1") (pinfunction "1_1") (pintype "passive"))
      (node (ref "R15") (pin "2") (pinfunction "2_2") (pintype "passive"))
    )
    (net (code "29") (name "Net-(Q3-C)") (class "Default")
      (node (ref "C12") (pin "1") (pinfunction "1_1") (pintype "passive"))
      (node (ref "Q3") (pin "3") (pinfunction "C_3") (pintype "passive"))
      (node (ref "R18") (pin "1") (pinfunction "1_1") (pintype "passive"))
    )
    (net (code "30") (name "Net-(R6-Pad2)") (class "Default")
      (node (ref "R6") (pin "2") (pinfunction "2_2") (pintype "passive"))
      (node (ref "U1") (pin "GND") (pinfunction "GND_GND") (pintype "bidirectional"))
      (node (ref "U1") (pin "GND1") (pinfunction "GND_GND1") (pintype "bidirectional"))
    )
    (net (code "31") (name "Net-(R13-Pad2)") (class "Default")
      (node (ref "R13") (pin "2") (pinfunction "2_2") (pintype "passive"))
      (node (ref "U$1") (pin "A") (pinfunction "A_A") (pintype "bidirectional"))
    )
    (net (code "32") (name "Net-(R21-Pad2)") (class "Default")
      (node (ref "R21") (pin "2") (pinfunction "2_2") (pintype "passive"))
      (node (ref "R4") (pin "1") (pinfunction "1_1") (pintype "passive"))
      (node (ref "T2") (pin "B") (pinfunction "B_B") (pintype "passive"))
    )
    (net (code "33") (name "Net-(T1A-D)") (class "Default")
      (node (ref "T1") (pin "1") (pinfunction "D_1") (pintype "passive"))
      (node (ref "T1") (pin "8") (pinfunction "D_8") (pintype "passive"))
    )
    (net (code "34") (name "Net-(T1A-G)") (class "Default")
      (node (ref "T1") (pin "4") (pinfunction "G_4") (pintype "passive"))
      (node (ref "U$7") (pin "1") (pinfunction "0D_1") (pintype "bidirectional"))
    )
    (net (code "35") (name "Net-(T1B-G)") (class "Default")
      (node (ref "T1") (pin "5") (pinfunction "G_5") (pintype "passive"))
      (node (ref "U$7") (pin "3") (pinfunction "0C_3") (pintype "bidirectional"))
    )
    (net (code "36") (name "Net-(U$4-2.OUT)") (class "Default")
      (node (ref "R7") (pin "1") (pinfunction "1_1") (pintype "passive"))
      (node (ref "U$4") (pin "2") (pinfunction "2.OUT_2") (pintype "bidirectional"))
    )
    (net (code "37") (name "Net-(U$6-PROG)") (class "Default")
      (node (ref "R62") (pin "2") (pinfunction "2_2") (pintype "passive"))
      (node (ref "U$6") (pin "2") (pinfunction "PROG_2") (pintype "bidirectional"))
    )
    (net (code "38") (name "Net-(U$6-~{CHRG})") (class "Default")
      (node (ref "R63") (pin "1") (pinfunction "1_1") (pintype "passive"))
      (node (ref "U$6") (pin "7") (pinfunction "~{CHRG}_7") (pintype "bidirectional"))
    )
    (net (code "39") (name "Net-(U$6-~{STDBY})") (class "Default")
      (node (ref "R64") (pin "1") (pinfunction "1_1") (pintype "passive"))
      (node (ref "U$6") (pin "6") (pinfunction "~{STDBY}_6") (pintype "bidirectional"))
    )
    (net (code "40") (name "Net-(U$7-CS)") (class "Default")
      (node (ref "R66") (pin "2") (pinfunction "2_2") (pintype "passive"))
      (node (ref "U$7") (pin "2") (pinfunction "CS_2") (pintype "bidirectional"))
    )
    (net (code "41") (name "Net-(U$7-GND)") (class "Default")
      (node (ref "BT1") (pin "-") (pinfunction "-_-") (pintype "power_in"))
      (node (ref "C1") (pin "-") (pinfunction "-_-") (pintype "passive"))
      (node (ref "C40") (pin "2") (pinfunction "2_2") (pintype "passive"))
      (node (ref "T1") (pin "2") (pinfunction "S_2") (pintype "passive"))
      (node (ref "T1") (pin "3") (pinfunction "S_3") (pintype "passive"))
      (node (ref "U$7") (pin "6") (pinfunction "GND_6") (pintype "bidirectional"))
    )
    (net (code "42") (name "Net-(U$7-VCC)") (class "Default")
      (node (ref "C40") (pin "1") (pinfunction "1_1") (pintype "passive"))
      (node (ref "R65") (pin "1") (pinfunction "1_1") (pintype "passive"))
      (node (ref "U$7") (pin "5") (pinfunction "VCC_5") (pintype "bidirectional"))
    )
    (net (code "43") (name "Net-(U$18-2.C2P)") (class "Default")
      (node (ref "C6") (pin "2") (pinfunction "2_2") (pintype "passive"))
      (node (ref "U$18") (pin "P$2") (pinfunction "2.C2P_P$2") (pintype "bidirectional"))
    )
    (net (code "44") (name "Net-(U$18-3.C2N)") (class "Default")
      (node (ref "C6") (pin "1") (pinfunction "1_1") (pintype "passive"))
      (node (ref "U$18") (pin "P$3") (pinfunction "3.C2N_P$3") (pintype "bidirectional"))
    )
    (net (code "45") (name "Net-(U$18-4.C1P)") (class "Default")
      (node (ref "C36") (pin "2") (pinfunction "2_2") (pintype "passive"))
      (node (ref "U$18") (pin "P$4") (pinfunction "4.C1P_P$4") (pintype "bidirectional"))
    )
    (net (code "46") (name "Net-(U$18-5.C1N)") (class "Default")
      (node (ref "C36") (pin "1") (pinfunction "1_1") (pintype "passive"))
      (node (ref "U$18") (pin "P$5") (pinfunction "5.C1N_P$5") (pintype "bidirectional"))
    )
    (net (code "47") (name "Net-(U$18-14.RES#)") (class "Default")
      (node (ref "C5") (pin "2") (pinfunction "2_2") (pintype "passive"))
      (node (ref "R38") (pin "2") (pinfunction "2_2") (pintype "passive"))
      (node (ref "U$18") (pin "P$14") (pinfunction "14.RES#_P$14") (pintype "bidirectional"))
    )
    (net (code "48") (name "Net-(U$18-26.IREF)") (class "Default")
      (node (ref "R39") (pin "1") (pinfunction "1_1") (pintype "passive"))
      (node (ref "U$18") (pin "P$26") (pinfunction "26.IREF_P$26") (pintype "bidirectional"))
    )
    (net (code "49") (name "Net-(U$18-27.VCOMH)") (class "Default")
      (node (ref "C7") (pin "2") (pinfunction "2_2") (pintype "passive"))
      (node (ref "U$18") (pin "P$27") (pinfunction "27.VCOMH_P$27") (pintype "bidirectional"))
    )
    (net (code "50") (name "Net-(U$18-28.VCC)") (class "Default")
      (node (ref "C37") (pin "2") (pinfunction "2_2") (pintype "passive"))
      (node (ref "U$18") (pin "P$28") (pinfunction "28.VCC_P$28") (pintype "bidirectional"))
    )
    (net (code "51") (name "Net-(U1-VBUS)") (class "Default")
      (node (ref "R7") (pin "2") (pinfunction "2_2") (pintype "passive"))
      (node (ref "U1") (pin "VBUS1") (pinfunction "VBUS_VBUS1") (pintype "bidirectional"))
    )
    (net (code "52") (name "Net-(VR1-CW)") (class "Default")
      (node (ref "R16") (pin "1") (pinfunction "1_1") (pintype "passive"))
      (node (ref "R17") (pin "2") (pinfunction "2_2") (pintype "passive"))
      (node (ref "VR1") (pin "3") (pinfunction "CW_3") (pintype "passive"))
    )
    (net (code "53") (name "OSC32_IN") (class "Default")
      (node (ref "C21") (pin "2") (pinfunction "2_2") (pintype "passive"))
      (node (ref "IC2") (pin "19") (pinfunction "19_19") (pintype "bidirectional"))
      (node (ref "U$8") (pin "1") (pinfunction "1.XIN_1") (pintype "bidirectional"))
    )
    (net (code "54") (name "OSC32_OUT") (class "Default")
      (node (ref "C20") (pin "2") (pinfunction "2_2") (pintype "passive"))
      (node (ref "IC2") (pin "18") (pinfunction "18_18") (pintype "bidirectional"))
      (node (ref "U$8") (pin "2") (pinfunction "2.XIN_2") (pintype "bidirectional"))
    )
    (net (code "55") (name "RST") (class "Default")
      (node (ref "C22") (pin "1") (pinfunction "1_1") (pintype "passive"))
      (node (ref "IC2") (pin "16") (pinfunction "16_16") (pintype "bidirectional"))
      (node (ref "JP1") (pin "6") (pinfunction "6_6") (pintype "passive"))
      (node (ref "R2") (pin "1") (pinfunction "1_1") (pintype "passive"))
      (node (ref "S1") (pin "1") (pinfunction "1_1") (pintype "passive"))
      (node (ref "S1") (pin "2") (pinfunction "2_2") (pintype "passive"))
    )
    (net (code "56") (name "RX") (class "Default")
      (node (ref "IC2") (pin "4") (pinfunction "4_4") (pintype "bidirectional"))
      (node (ref "JP1") (pin "4") (pinfunction "4_4") (pintype "passive"))
    )
    (net (code "57") (name "TEMPRATURE") (class "Default")
      (node (ref "IC2") (pin "5") (pinfunction "5_5") (pintype "bidirectional"))
      (node (ref "IC5") (pin "4") (pinfunction "OUT_4") (pintype "output"))
      (node (ref "R20") (pin "2") (pinfunction "2_2") (pintype "passive"))
    )
    (net (code "58") (name "TEST") (class "Default")
      (node (ref "IC2") (pin "17") (pinfunction "17_17") (pintype "bidirectional"))
      (node (ref "JP1") (pin "5") (pinfunction "5_5") (pintype "passive"))
    )
    (net (code "59") (name "TX") (class "Default")
      (node (ref "IC2") (pin "3") (pinfunction "3_3") (pintype "bidirectional"))
      (node (ref "JP1") (pin "3") (pinfunction "3_3") (pintype "passive"))
    )
    (net (code "60") (name "VBUS") (class "Default")
      (node (ref "C38") (pin "A") (pinfunction "+_A") (pintype "passive"))
      (node (ref "D5") (pin "A") (pinfunction "A_A") (pintype "passive"))
      (node (ref "D6") (pin "A") (pinfunction "A_A") (pintype "passive"))
      (node (ref "U$4") (pin "1") (pinfunction "1.IN_1") (pintype "bidirectional"))
      (node (ref "U$6") (pin "4") (pinfunction "VCC_4") (pintype "bidirectional"))
      (node (ref "U$6") (pin "8") (pinfunction "CE_8") (pintype "bidirectional"))
    )
    (net (code "61") (name "VCC") (class "Default")
      (node (ref "C3") (pin "1") (pinfunction "1_1") (pintype "passive"))
      (node (ref "IC1") (pin "3") (pinfunction "IN_3") (pintype "input"))
      (node (ref "SW1") (pin "CH1A") (pinfunction "CH1A_CH1A") (pintype "bidirectional"))
    )
    (net (code "62") (name "VDD") (class "Default")
      (node (ref "C13") (pin "1") (pinfunction "1_1") (pintype "passive"))
      (node (ref "C2") (pin "1") (pinfunction "1_1") (pintype "passive"))
      (node (ref "IC1") (pin "2") (pinfunction "OUT_2") (pintype "output"))
      (node (ref "IC1") (pin "4") (pinfunction "OUT_4") (pintype "output"))
      (node (ref "IC2") (pin "1") (pinfunction "1_1") (pintype "bidirectional"))
      (node (ref "IC5") (pin "5") (pinfunction "V+_5") (pintype "power_in"))
      (node (ref "J1") (pin "1") (pinfunction "1_1") (pintype "passive"))
      (node (ref "JP1") (pin "1") (pinfunction "1_1") (pintype "passive"))
      (node (ref "R11") (pin "2") (pinfunction "2_2") (pintype "passive"))
      (node (ref "R18") (pin "2") (pinfunction "2_2") (pintype "passive"))
      (node (ref "R2") (pin "2") (pinfunction "2_2") (pintype "passive"))
      (node (ref "R3") (pin "2") (pinfunction "2_2") (pintype "passive"))
      (node (ref "R38") (pin "1") (pinfunction "1_1") (pintype "passive"))
      (node (ref "R40") (pin "2") (pinfunction "2_2") (pintype "passive"))
      (node (ref "R41") (pin "1") (pinfunction "1_1") (pintype "passive"))
      (node (ref "R5") (pin "1") (pinfunction "1_1") (pintype "passive"))
      (node (ref "U$18") (pin "P$11") (pinfunction "11.BS1_P$11") (pintype "bidirectional"))
      (node (ref "U$18") (pin "P$6") (pinfunction "6.VBAT_P$6") (pintype "bidirectional"))
      (node (ref "U$18") (pin "P$9") (pinfunction "9.VDD_P$9") (pintype "bidirectional"))
      (node (ref "U$2") (pin "P2") (pinfunction "2_P2") (pintype "bidirectional"))
      (node (ref "U2") (pin "1") (pinfunction "+VS_1") (pintype "bidirectional"))
    )
    (net (code "63") (name "unconnected-(IC2-Pad2)") (class "Default")
      (node (ref "IC2") (pin "2") (pinfunction "2_2") (pintype "bidirectional"))
    )
    (net (code "64") (name "unconnected-(IC2-Pad7)") (class "Default")
      (node (ref "IC2") (pin "7") (pinfunction "7_7") (pintype "bidirectional"))
    )
    (net (code "65") (name "unconnected-(IC2-Pad8)") (class "Default")
      (node (ref "IC2") (pin "8") (pinfunction "8_8") (pintype "bidirectional"))
    )
    (net (code "66") (name "unconnected-(IC2-Pad9)") (class "Default")
      (node (ref "IC2") (pin "9") (pinfunction "9_9") (pintype "bidirectional"))
    )
    (net (code "67") (name "unconnected-(IC2-Pad13)") (class "Default")
      (node (ref "IC2") (pin "13") (pinfunction "13_13") (pintype "bidirectional"))
    )
    (net (code "68") (name "unconnected-(SW1-PadCH1B)") (class "Default")
      (node (ref "SW1") (pin "CH1B") (pinfunction "CH1B_CH1B") (pintype "bidirectional"))
    )
    (net (code "69") (name "unconnected-(SW1-PadCH2A)") (class "Default")
      (node (ref "SW1") (pin "CH2A") (pinfunction "CH2A_CH2A") (pintype "bidirectional"))
    )
    (net (code "70") (name "unconnected-(SW1-PadCH2B)") (class "Default")
      (node (ref "SW1") (pin "CH2B") (pinfunction "CH2B_CH2B") (pintype "bidirectional"))
    )
    (net (code "71") (name "unconnected-(SW1-PadCOM2)") (class "Default")
      (node (ref "SW1") (pin "COM2") (pinfunction "COM2_COM2") (pintype "bidirectional"))
    )
    (net (code "72") (name "unconnected-(U$7-TD-Pad4)") (class "Default")
      (node (ref "U$7") (pin "4") (pinfunction "TD_4") (pintype "bidirectional"))
    )
    (net (code "73") (name "unconnected-(U$18-1.NC(GND)-PadP$1)") (class "Default")
      (node (ref "U$18") (pin "P$1") (pinfunction "1.NC(GND)_P$1") (pintype "bidirectional"))
    )
    (net (code "74") (name "unconnected-(U$18-7.NC-PadP$7)") (class "Default")
      (node (ref "U$18") (pin "P$7") (pinfunction "7.NC_P$7") (pintype "bidirectional"))
    )
    (net (code "75") (name "unconnected-(U$18-30.NC(GND)-PadP$30)") (class "Default")
      (node (ref "U$18") (pin "P$30") (pinfunction "30.NC(GND)_P$30") (pintype "bidirectional"))
    )
    (net (code "76") (name "unconnected-(U1-D+-PadD+1)") (class "Default")
      (node (ref "U1") (pin "D+1") (pinfunction "D+_D+1") (pintype "bidirectional"))
    )
    (net (code "77") (name "unconnected-(U1-D--PadD-1)") (class "Default")
      (node (ref "U1") (pin "D-1") (pinfunction "D-_D-1") (pintype "bidirectional"))
    )
    (net (code "78") (name "unconnected-(U1-USBID-PadID1)") (class "Default")
      (node (ref "U1") (pin "ID1") (pinfunction "USBID_ID1") (pintype "bidirectional"))
    )
    (net (code "79") (name "unconnected-(VR1-CCW-Pad1)") (class "Default")
      (node (ref "VR1") (pin "1") (pinfunction "CCW_1") (pintype "passive"))
    )
  )
)
